# mrShark_13.net
KiCad netlist of a schematic drawn in EAGLE
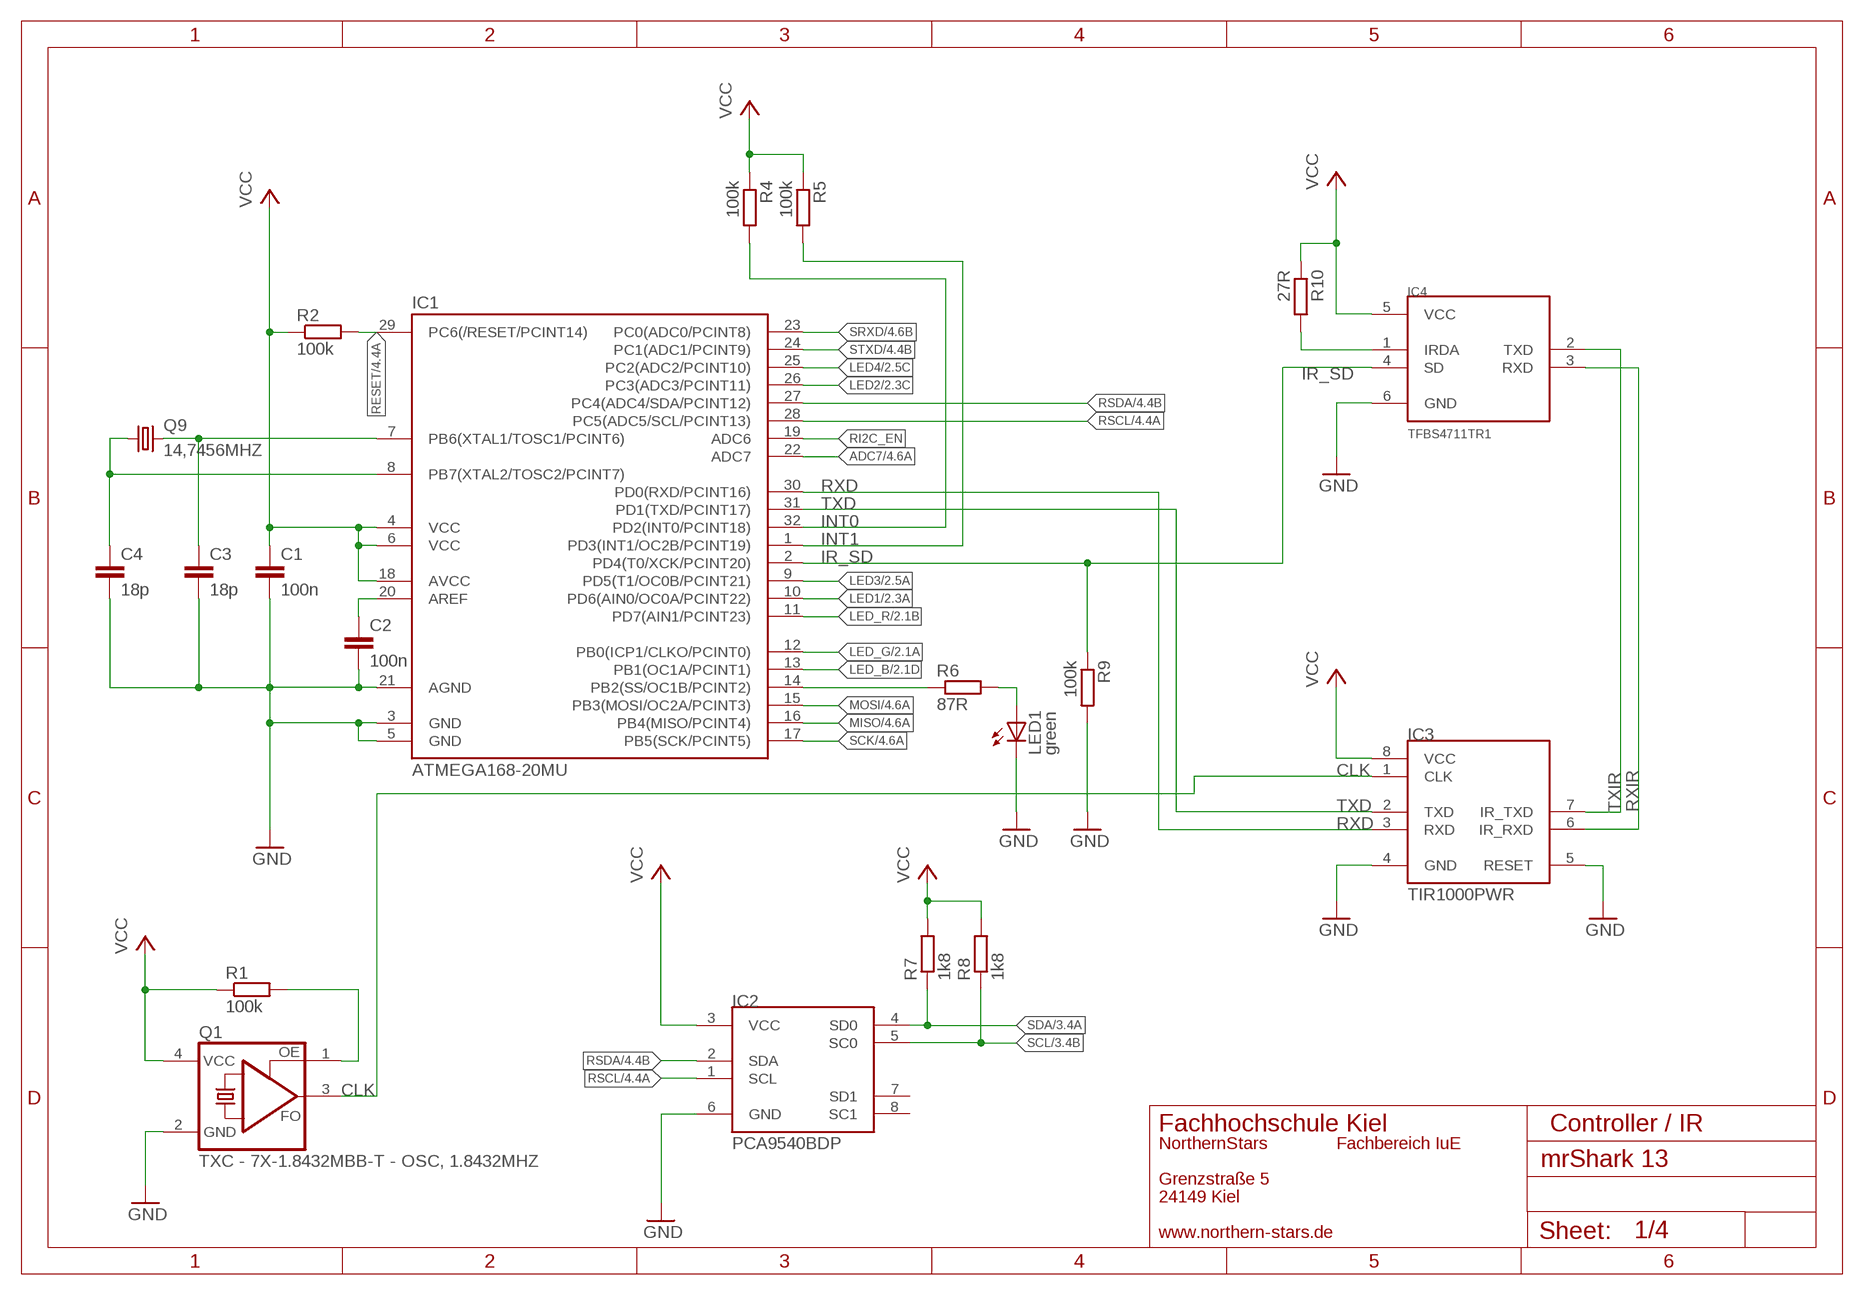
[diagram p0: schematic, sheet 1]
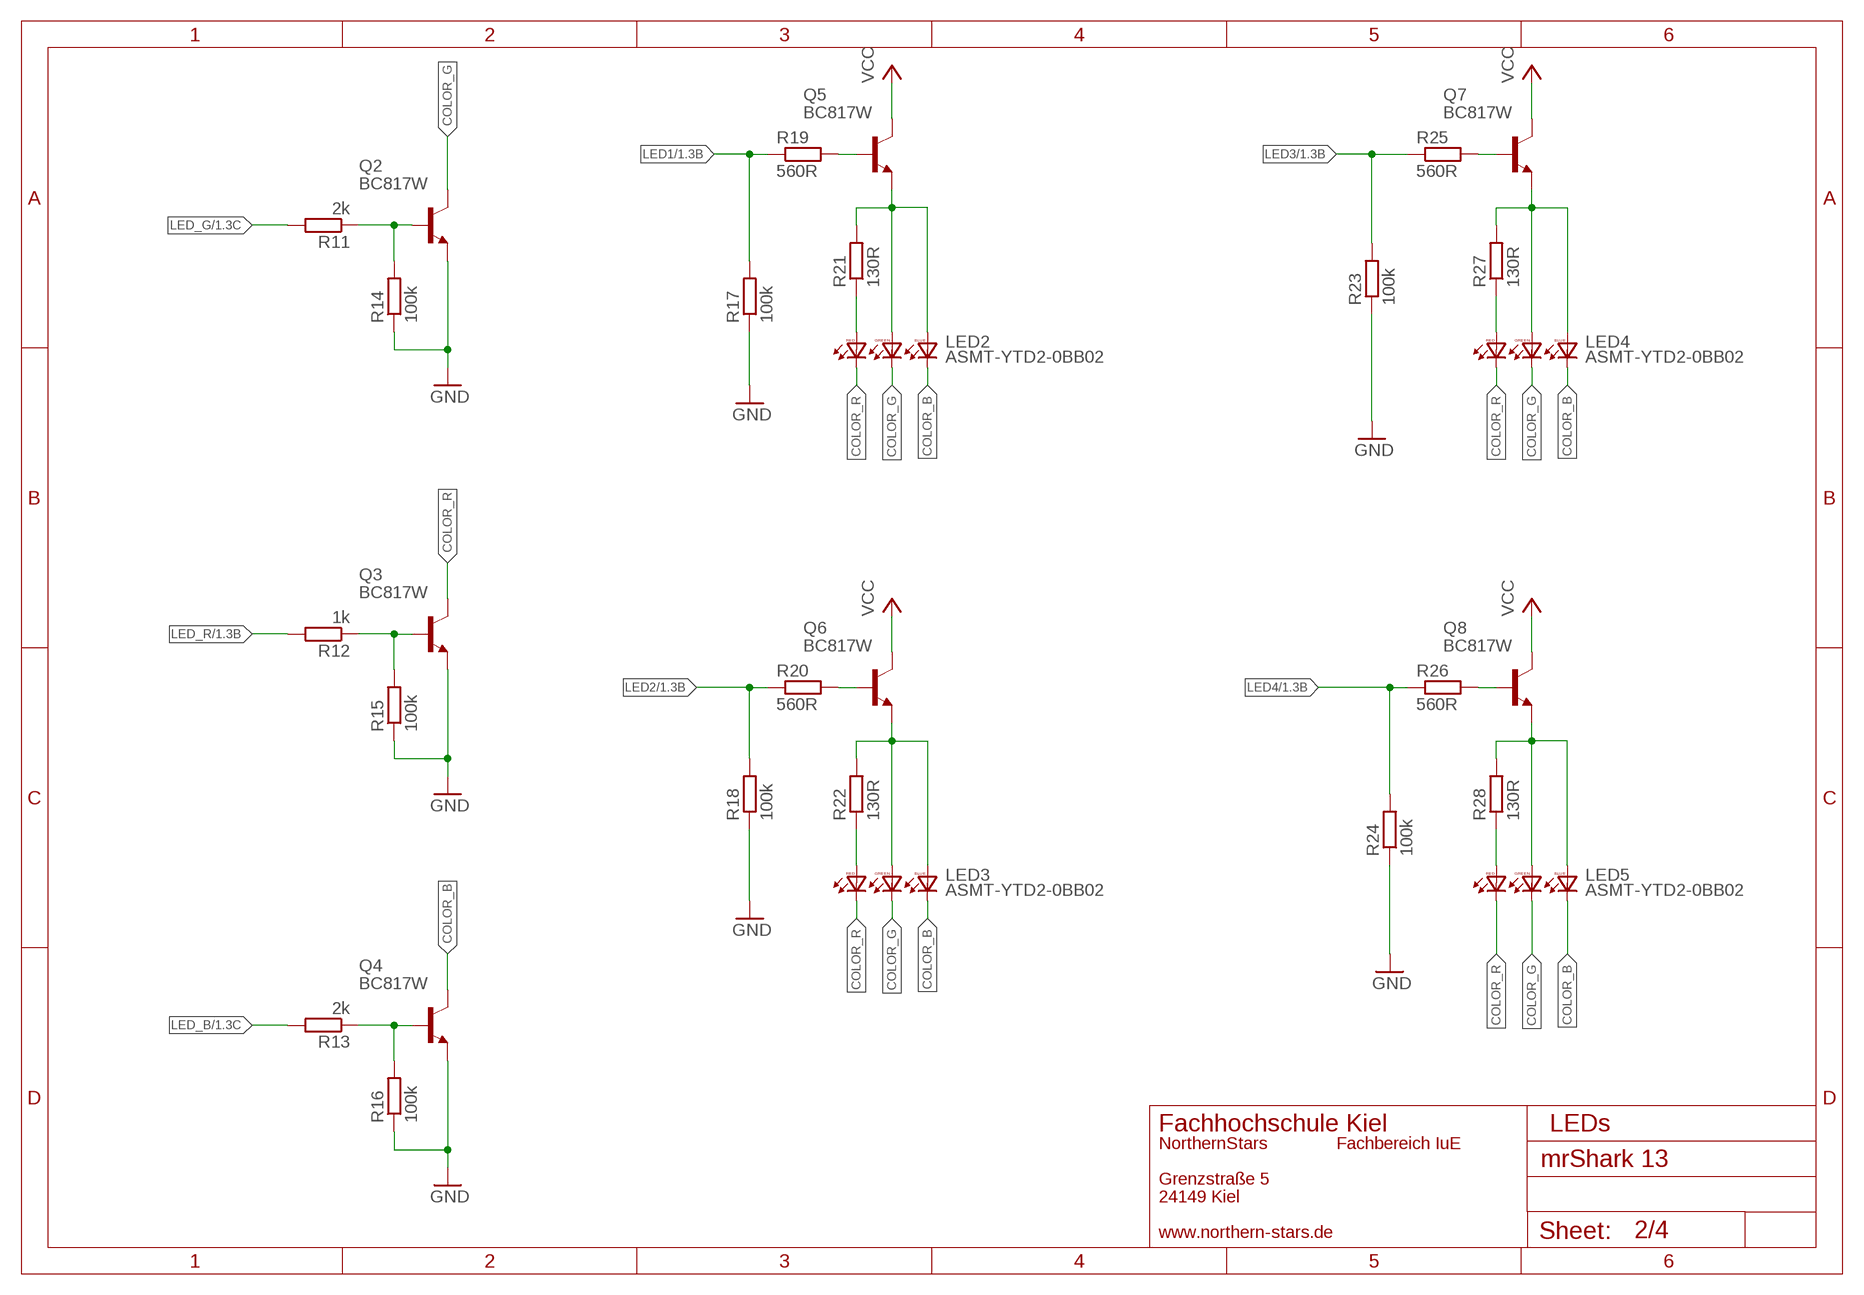
[diagram p1: schematic, sheet 2]
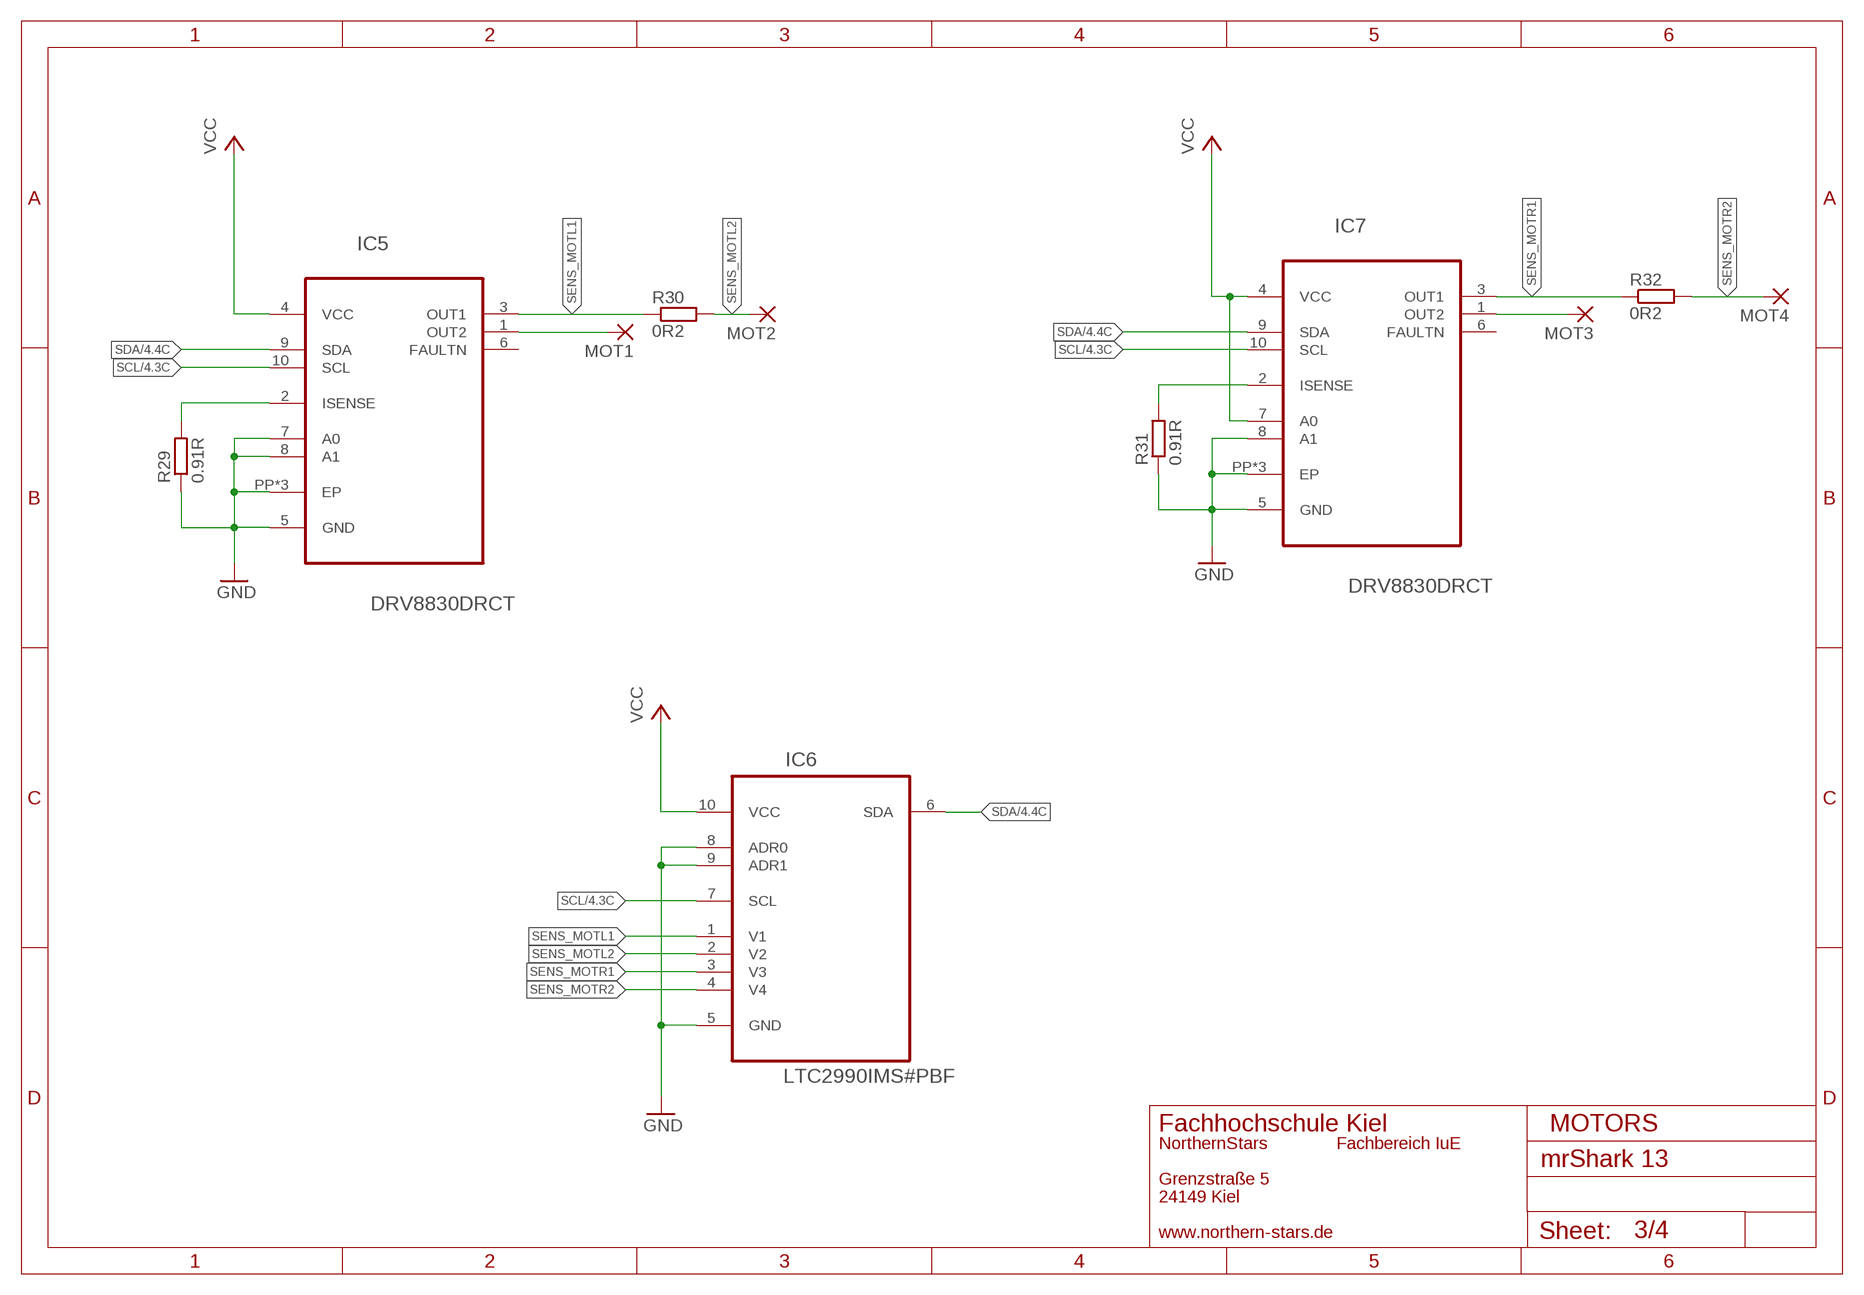
[diagram p2: schematic, sheet 3]
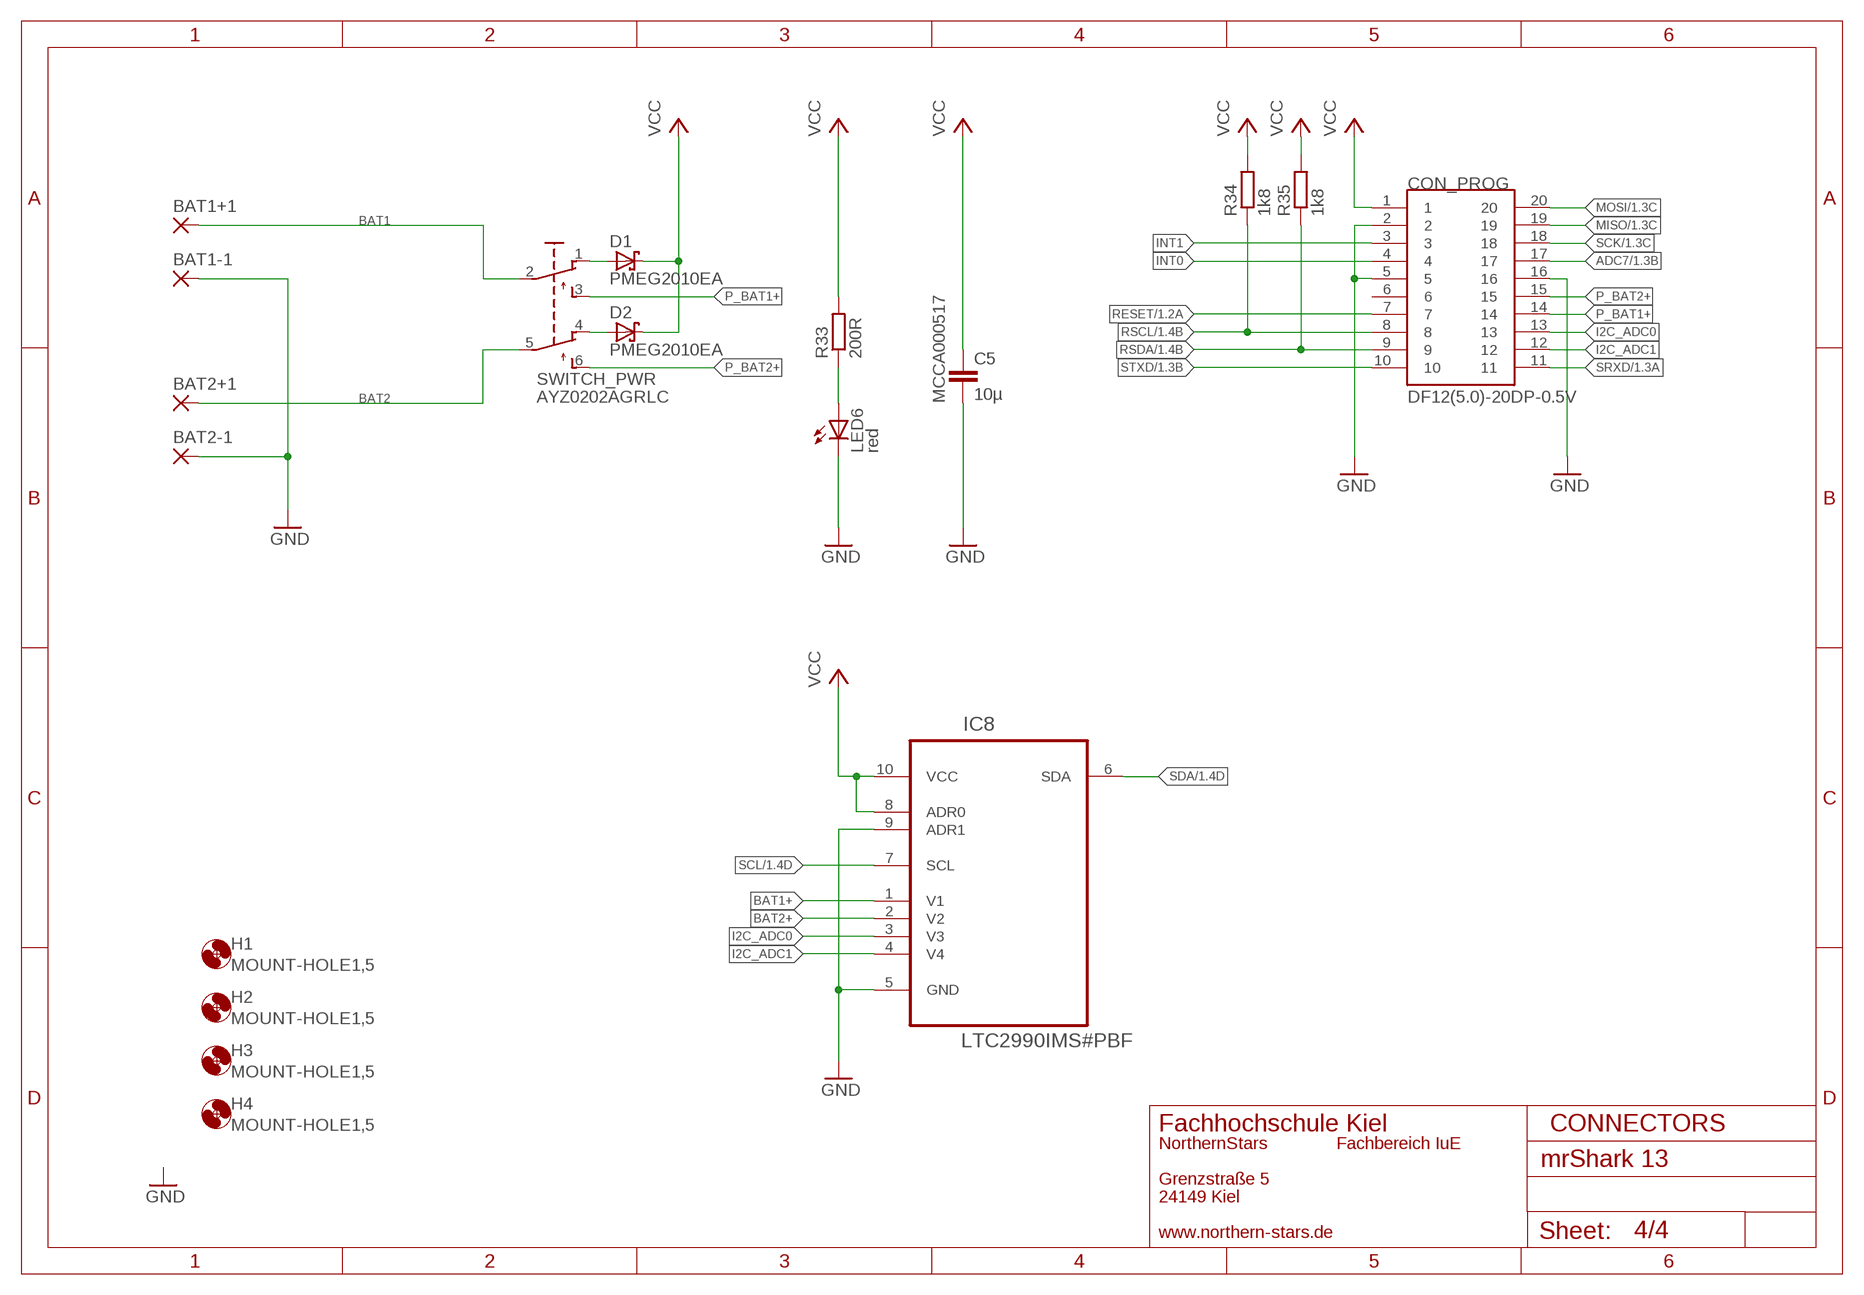
[diagram p3: schematic, sheet 4]

(export (version "E")
  (design (tool "Eeschema 10.0.6"))
  (components
    (comp (ref "C1")
      (value "100n")
      (footprint "eagle-import:C0201")
      (libsource (lib "eagle-import") (part "C-EUC0201"))
    )
    (comp (ref "C2")
      (value "100n")
      (footprint "eagle-import:C0201")
      (libsource (lib "eagle-import") (part "C-EUC0201"))
    )
    (comp (ref "C3")
      (value "18p")
      (footprint "eagle-import:C0201")
      (libsource (lib "eagle-import") (part "C-EUC0201"))
    )
    (comp (ref "C4")
      (value "18p")
      (footprint "eagle-import:C0201")
      (libsource (lib "eagle-import") (part "C-EUC0201"))
    )
    (comp (ref "IC1")
      (value "ATMEGA168-20MU")
      (footprint "eagle-import:MLF32")
      (libsource (lib "eagle-import") (part "ATMEGA48/88/168-MU"))
    )
    (comp (ref "IC2")
      (value "PCA9540BDP")
      (footprint "eagle-import:TSSOP8")
      (libsource (lib "eagle-import") (part "PCA9540TSSOP8"))
    )
    (comp (ref "IC3")
      (value "TIR1000PWR")
      (footprint "eagle-import:PW_R-PDSO-G08")
      (libsource (lib "eagle-import") (part "TIR1000PWR"))
    )
    (comp (ref "IC4")
      (value "TFBS4711TR1")
      (footprint "eagle-import:TFBS4711")
      (libsource (lib "eagle-import") (part "TFBS4711TR1"))
    )
    (comp (ref "LED1")
      (value "green")
      (footprint "eagle-import:CHIPLED_0603")
      (libsource (lib "eagle-import") (part "LEDCHIPLED_0603"))
    )
    (comp (ref "Q1")
      (value "TXC - 7X-1.8432MBB-T - OSC, 1.8432MHZ")
      (footprint "eagle-import:3.2X2.5")
      (libsource (lib "eagle-import") (part "7X-SERIES"))
    )
    (comp (ref "Q9")
      (value "14,7456MHZ")
      (footprint "eagle-import:TXC_7B_SERIES")
      (libsource (lib "eagle-import") (part "TXC-7B-SERIESSMD"))
    )
    (comp (ref "R1")
      (value "100k")
      (footprint "eagle-import:R0201")
      (libsource (lib "eagle-import") (part "R-EU_R0201"))
    )
    (comp (ref "R2")
      (value "100k")
      (footprint "eagle-import:R0201")
      (libsource (lib "eagle-import") (part "R-EU_R0201"))
    )
    (comp (ref "R4")
      (value "100k")
      (footprint "eagle-import:R0201")
      (libsource (lib "eagle-import") (part "R-EU_R0201"))
    )
    (comp (ref "R5")
      (value "100k")
      (footprint "eagle-import:R0201")
      (libsource (lib "eagle-import") (part "R-EU_R0201"))
    )
    (comp (ref "R6")
      (value "87R")
      (footprint "eagle-import:R0201")
      (libsource (lib "eagle-import") (part "R-EU_R0201"))
    )
    (comp (ref "R7")
      (value "1k8")
      (footprint "eagle-import:R0201")
      (libsource (lib "eagle-import") (part "R-EU_R0201"))
    )
    (comp (ref "R8")
      (value "1k8")
      (footprint "eagle-import:R0201")
      (libsource (lib "eagle-import") (part "R-EU_R0201"))
    )
    (comp (ref "R9")
      (value "100k")
      (footprint "eagle-import:R0201")
      (libsource (lib "eagle-import") (part "R-EU_R0201"))
    )
    (comp (ref "R10")
      (value "27R")
      (footprint "eagle-import:R0201")
      (libsource (lib "eagle-import") (part "R-EU_R0201"))
    )
    (comp (ref "IC5")
      (value "DRV8830DRCT")
      (footprint "eagle-import:S-PDSO-N10")
      (libsource (lib "eagle-import") (part "DRV8830DGQRWSON"))
    )
    (comp (ref "IC6")
      (value "LTC2990IMS#PBF")
      (footprint "eagle-import:SOP50P490X110-10N")
      (libsource (lib "eagle-import") (part "LTC2990IMSPBF"))
    )
    (comp (ref "IC7")
      (value "DRV8830DRCT")
      (footprint "eagle-import:S-PDSO-N10")
      (libsource (lib "eagle-import") (part "DRV8830DGQRWSON"))
    )
    (comp (ref "MOT1")
      (value "1,6/0,9")
      (footprint "eagle-import:1,6_0,9")
      (libsource (lib "eagle-import") (part "1,6/0,9"))
    )
    (comp (ref "MOT2")
      (value "1,6/0,9")
      (footprint "eagle-import:1,6_0,9")
      (libsource (lib "eagle-import") (part "1,6/0,9"))
    )
    (comp (ref "MOT3")
      (value "1,6/0,9")
      (footprint "eagle-import:1,6_0,9")
      (libsource (lib "eagle-import") (part "1,6/0,9"))
    )
    (comp (ref "MOT4")
      (value "1,6/0,9")
      (footprint "eagle-import:1,6_0,9")
      (libsource (lib "eagle-import") (part "1,6/0,9"))
    )
    (comp (ref "R29")
      (value "0.91R")
      (footprint "eagle-import:R0603")
      (libsource (lib "eagle-import") (part "R-EU_R0603"))
    )
    (comp (ref "R30")
      (value "0R2")
      (footprint "eagle-import:R0603")
      (libsource (lib "eagle-import") (part "R-EU_R0603"))
    )
    (comp (ref "R31")
      (value "0.91R")
      (footprint "eagle-import:R0603")
      (libsource (lib "eagle-import") (part "R-EU_R0603"))
    )
    (comp (ref "R32")
      (value "0R2")
      (footprint "eagle-import:R0603")
      (libsource (lib "eagle-import") (part "R-EU_R0603"))
    )
    (comp (ref "BAT1+1")
      (value "1,6/0,9")
      (footprint "eagle-import:1,6_0,9")
      (libsource (lib "eagle-import") (part "1,6/0,9"))
    )
    (comp (ref "BAT1-1")
      (value "1,6/0,9")
      (footprint "eagle-import:1,6_0,9")
      (libsource (lib "eagle-import") (part "1,6/0,9"))
    )
    (comp (ref "BAT2+1")
      (value "1,6/0,9")
      (footprint "eagle-import:1,6_0,9")
      (libsource (lib "eagle-import") (part "1,6/0,9"))
    )
    (comp (ref "BAT2-1")
      (value "1,6/0,9")
      (footprint "eagle-import:1,6_0,9")
      (libsource (lib "eagle-import") (part "1,6/0,9"))
    )
    (comp (ref "C5")
      (value "10µ")
      (footprint "eagle-import:C0603K")
      (libsource (lib "eagle-import") (part "C-EUC0603K"))
    )
    (comp (ref "CON_PROG")
      (value "DF12(5.0)-20DP-0.5V")
      (footprint "eagle-import:DF12-20DP")
      (libsource (lib "eagle-import") (part "DF12-20DP"))
    )
    (comp (ref "D1")
      (value "PMEG2010EA")
      (footprint "eagle-import:SOD323-R")
      (libsource (lib "eagle-import") (part "PMEG2010EAR"))
    )
    (comp (ref "D2")
      (value "PMEG2010EA")
      (footprint "eagle-import:SOD323-R")
      (libsource (lib "eagle-import") (part "PMEG2010EAR"))
    )
    (comp (ref "H1")
      (value "MOUNT-HOLE1,5")
      (footprint "eagle-import:1,5")
      (libsource (lib "eagle-import") (part "MOUNT-HOLE1,5"))
    )
    (comp (ref "H2")
      (value "MOUNT-HOLE1,5")
      (footprint "eagle-import:1,5")
      (libsource (lib "eagle-import") (part "MOUNT-HOLE1,5"))
    )
    (comp (ref "H3")
      (value "MOUNT-HOLE1,5")
      (footprint "eagle-import:1,5")
      (libsource (lib "eagle-import") (part "MOUNT-HOLE1,5"))
    )
    (comp (ref "H4")
      (value "MOUNT-HOLE1,5")
      (footprint "eagle-import:1,5")
      (libsource (lib "eagle-import") (part "MOUNT-HOLE1,5"))
    )
    (comp (ref "IC8")
      (value "LTC2990IMS#PBF")
      (footprint "eagle-import:SOP50P490X110-10N")
      (libsource (lib "eagle-import") (part "LTC2990IMSPBF"))
    )
    (comp (ref "LED6")
      (value "red")
      (footprint "eagle-import:CHIPLED_0603")
      (libsource (lib "eagle-import") (part "LEDCHIPLED_0603"))
    )
    (comp (ref "R33")
      (value "200R")
      (footprint "eagle-import:R0201")
      (libsource (lib "eagle-import") (part "R-EU_R0201"))
    )
    (comp (ref "R34")
      (value "1k8")
      (footprint "eagle-import:R0201")
      (libsource (lib "eagle-import") (part "R-EU_R0201"))
    )
    (comp (ref "R35")
      (value "1k8")
      (footprint "eagle-import:R0201")
      (libsource (lib "eagle-import") (part "R-EU_R0201"))
    )
    (comp (ref "SWITCH_PWR")
      (value "AYZ0202AGRLC")
      (footprint "eagle-import:AYZ0202AGLRC")
      (libsource (lib "eagle-import") (part "AYZ0202AGRLC"))
    )
    (comp (ref "LED2")
      (value "ASMT-YTD2-0BB02")
      (footprint "eagle-import:PLCC6K")
      (libsource (lib "eagle-import") (part "PLCC6K"))
    )
    (comp (ref "LED3")
      (value "ASMT-YTD2-0BB02")
      (footprint "eagle-import:PLCC6K")
      (libsource (lib "eagle-import") (part "PLCC6K"))
    )
    (comp (ref "LED4")
      (value "ASMT-YTD2-0BB02")
      (footprint "eagle-import:PLCC6K")
      (libsource (lib "eagle-import") (part "PLCC6K"))
    )
    (comp (ref "LED5")
      (value "ASMT-YTD2-0BB02")
      (footprint "eagle-import:PLCC6K")
      (libsource (lib "eagle-import") (part "PLCC6K"))
    )
    (comp (ref "Q2")
      (value "BC817W")
      (footprint "eagle-import:SOT323-BEC")
      (libsource (lib "eagle-import") (part "BC817W"))
    )
    (comp (ref "Q3")
      (value "BC817W")
      (footprint "eagle-import:SOT323-BEC")
      (libsource (lib "eagle-import") (part "BC817W"))
    )
    (comp (ref "Q4")
      (value "BC817W")
      (footprint "eagle-import:SOT323-BEC")
      (libsource (lib "eagle-import") (part "BC817W"))
    )
    (comp (ref "Q5")
      (value "BC817W")
      (footprint "eagle-import:SOT323-BEC")
      (libsource (lib "eagle-import") (part "BC817W"))
    )
    (comp (ref "Q6")
      (value "BC817W")
      (footprint "eagle-import:SOT323-BEC")
      (libsource (lib "eagle-import") (part "BC817W"))
    )
    (comp (ref "Q7")
      (value "BC817W")
      (footprint "eagle-import:SOT323-BEC")
      (libsource (lib "eagle-import") (part "BC817W"))
    )
    (comp (ref "Q8")
      (value "BC817W")
      (footprint "eagle-import:SOT323-BEC")
      (libsource (lib "eagle-import") (part "BC817W"))
    )
    (comp (ref "R11")
      (value "2k")
      (footprint "eagle-import:R0201")
      (libsource (lib "eagle-import") (part "R-EU_R0201"))
    )
    (comp (ref "R12")
      (value "1k")
      (footprint "eagle-import:R0201")
      (libsource (lib "eagle-import") (part "R-EU_R0201"))
    )
    (comp (ref "R13")
      (value "2k")
      (footprint "eagle-import:R0201")
      (libsource (lib "eagle-import") (part "R-EU_R0201"))
    )
    (comp (ref "R14")
      (value "100k")
      (footprint "eagle-import:R0201")
      (libsource (lib "eagle-import") (part "R-EU_R0201"))
    )
    (comp (ref "R15")
      (value "100k")
      (footprint "eagle-import:R0201")
      (libsource (lib "eagle-import") (part "R-EU_R0201"))
    )
    (comp (ref "R16")
      (value "100k")
      (footprint "eagle-import:R0201")
      (libsource (lib "eagle-import") (part "R-EU_R0201"))
    )
    (comp (ref "R17")
      (value "100k")
      (footprint "eagle-import:R0201")
      (libsource (lib "eagle-import") (part "R-EU_R0201"))
    )
    (comp (ref "R18")
      (value "100k")
      (footprint "eagle-import:R0201")
      (libsource (lib "eagle-import") (part "R-EU_R0201"))
    )
    (comp (ref "R19")
      (value "560R")
      (footprint "eagle-import:R0201")
      (libsource (lib "eagle-import") (part "R-EU_R0201"))
    )
    (comp (ref "R20")
      (value "560R")
      (footprint "eagle-import:R0201")
      (libsource (lib "eagle-import") (part "R-EU_R0201"))
    )
    (comp (ref "R21")
      (value "130R")
      (footprint "eagle-import:R0201")
      (libsource (lib "eagle-import") (part "R-EU_R0201"))
    )
    (comp (ref "R22")
      (value "130R")
      (footprint "eagle-import:R0201")
      (libsource (lib "eagle-import") (part "R-EU_R0201"))
    )
    (comp (ref "R23")
      (value "100k")
      (footprint "eagle-import:R0201")
      (libsource (lib "eagle-import") (part "R-EU_R0201"))
    )
    (comp (ref "R24")
      (value "100k")
      (footprint "eagle-import:R0201")
      (libsource (lib "eagle-import") (part "R-EU_R0201"))
    )
    (comp (ref "R25")
      (value "560R")
      (footprint "eagle-import:R0201")
      (libsource (lib "eagle-import") (part "R-EU_R0201"))
    )
    (comp (ref "R26")
      (value "560R")
      (footprint "eagle-import:R0201")
      (libsource (lib "eagle-import") (part "R-EU_R0201"))
    )
    (comp (ref "R27")
      (value "130R")
      (footprint "eagle-import:R0201")
      (libsource (lib "eagle-import") (part "R-EU_R0201"))
    )
    (comp (ref "R28")
      (value "130R")
      (footprint "eagle-import:R0201")
      (libsource (lib "eagle-import") (part "R-EU_R0201"))
    )
  )
  (nets
    (net (code "1") (name "ADC7") (class "Default")
      (node (ref "CON_PROG") (pin "17") (pinfunction "17_17") (pintype "bidirectional"))
      (node (ref "IC1") (pin "22") (pinfunction "ADC7_22") (pintype "passive"))
    )
    (net (code "2") (name "BAT1") (class "Default")
      (node (ref "BAT1+1") (pin "1") (pinfunction "P_1") (pintype "passive"))
      (node (ref "SWITCH_PWR") (pin "2") (pinfunction "P_2") (pintype "passive"))
    )
    (net (code "3") (name "BAT1+") (class "Default")
      (node (ref "D1") (pin "A") (pinfunction "A_A") (pintype "passive"))
      (node (ref "IC8") (pin "1") (pinfunction "V1_1") (pintype "input"))
      (node (ref "SWITCH_PWR") (pin "1") (pinfunction "O_1") (pintype "passive"))
    )
    (net (code "4") (name "BAT2") (class "Default")
      (node (ref "BAT2+1") (pin "1") (pinfunction "P_1") (pintype "passive"))
      (node (ref "SWITCH_PWR") (pin "5") (pinfunction "P1_5") (pintype "passive"))
    )
    (net (code "5") (name "BAT2+") (class "Default")
      (node (ref "D2") (pin "A") (pinfunction "A_A") (pintype "passive"))
      (node (ref "IC8") (pin "2") (pinfunction "V2_2") (pintype "input"))
      (node (ref "SWITCH_PWR") (pin "4") (pinfunction "O1_4") (pintype "passive"))
    )
    (net (code "6") (name "CLK") (class "Default")
      (node (ref "IC3") (pin "1") (pinfunction "CLK_1") (pintype "bidirectional"))
      (node (ref "Q1") (pin "3") (pinfunction "FO_3") (pintype "output"))
    )
    (net (code "7") (name "COLOR_B") (class "Default")
      (node (ref "LED2") (pin "1") (pinfunction "BC_1") (pintype "passive"))
      (node (ref "LED3") (pin "1") (pinfunction "BC_1") (pintype "passive"))
      (node (ref "LED4") (pin "1") (pinfunction "BC_1") (pintype "passive"))
      (node (ref "LED5") (pin "1") (pinfunction "BC_1") (pintype "passive"))
      (node (ref "Q4") (pin "C") (pinfunction "C_C") (pintype "passive"))
    )
    (net (code "8") (name "COLOR_G") (class "Default")
      (node (ref "LED2") (pin "2") (pinfunction "GC_2") (pintype "passive"))
      (node (ref "LED3") (pin "2") (pinfunction "GC_2") (pintype "passive"))
      (node (ref "LED4") (pin "2") (pinfunction "GC_2") (pintype "passive"))
      (node (ref "LED5") (pin "2") (pinfunction "GC_2") (pintype "passive"))
      (node (ref "Q2") (pin "C") (pinfunction "C_C") (pintype "passive"))
    )
    (net (code "9") (name "COLOR_R") (class "Default")
      (node (ref "LED2") (pin "3") (pinfunction "RC_3") (pintype "passive"))
      (node (ref "LED3") (pin "3") (pinfunction "RC_3") (pintype "passive"))
      (node (ref "LED4") (pin "3") (pinfunction "RC_3") (pintype "passive"))
      (node (ref "LED5") (pin "3") (pinfunction "RC_3") (pintype "passive"))
      (node (ref "Q3") (pin "C") (pinfunction "C_C") (pintype "passive"))
    )
    (net (code "10") (name "GND") (class "Default")
      (node (ref "BAT1-1") (pin "1") (pinfunction "P_1") (pintype "passive"))
      (node (ref "BAT2-1") (pin "1") (pinfunction "P_1") (pintype "passive"))
      (node (ref "C1") (pin "2") (pinfunction "2_2") (pintype "passive"))
      (node (ref "C2") (pin "2") (pinfunction "2_2") (pintype "passive"))
      (node (ref "C3") (pin "2") (pinfunction "2_2") (pintype "passive"))
      (node (ref "C4") (pin "2") (pinfunction "2_2") (pintype "passive"))
      (node (ref "C5") (pin "2") (pinfunction "2_2") (pintype "passive"))
      (node (ref "CON_PROG") (pin "16") (pinfunction "16_16") (pintype "bidirectional"))
      (node (ref "CON_PROG") (pin "2") (pinfunction "2_2") (pintype "bidirectional"))
      (node (ref "CON_PROG") (pin "5") (pinfunction "5_5") (pintype "bidirectional"))
      (node (ref "IC1") (pin "21") (pinfunction "AGND_21") (pintype "power_in"))
      (node (ref "IC1") (pin "3") (pinfunction "GND_3") (pintype "power_in"))
      (node (ref "IC1") (pin "5") (pinfunction "GND_5") (pintype "power_in"))
      (node (ref "IC2") (pin "6") (pinfunction "GND_6") (pintype "bidirectional"))
      (node (ref "IC3") (pin "4") (pinfunction "GND_4") (pintype "bidirectional"))
      (node (ref "IC3") (pin "5") (pinfunction "RESET_5") (pintype "bidirectional"))
      (node (ref "IC4") (pin "6") (pinfunction "GND_6") (pintype "bidirectional"))
      (node (ref "IC5") (pin "5") (pinfunction "GND_5") (pintype "passive"))
      (node (ref "IC5") (pin "7") (pinfunction "A0_7") (pintype "input"))
      (node (ref "IC5") (pin "8") (pinfunction "A1_8") (pintype "input"))
      (node (ref "IC5") (pin "PP") (pinfunction "EP_PP") (pintype "passive"))
      (node (ref "IC5") (pin "PP@1") (pinfunction "EP_PP@1") (pintype "passive"))
      (node (ref "IC5") (pin "PP@2") (pinfunction "EP_PP@2") (pintype "passive"))
      (node (ref "IC6") (pin "5") (pinfunction "GND_5") (pintype "passive"))
      (node (ref "IC6") (pin "8") (pinfunction "ADR0_8") (pintype "input"))
      (node (ref "IC6") (pin "9") (pinfunction "ADR1_9") (pintype "input"))
      (node (ref "IC7") (pin "5") (pinfunction "GND_5") (pintype "passive"))
      (node (ref "IC7") (pin "8") (pinfunction "A1_8") (pintype "input"))
      (node (ref "IC7") (pin "PP") (pinfunction "EP_PP") (pintype "passive"))
      (node (ref "IC7") (pin "PP@1") (pinfunction "EP_PP@1") (pintype "passive"))
      (node (ref "IC7") (pin "PP@2") (pinfunction "EP_PP@2") (pintype "passive"))
      (node (ref "IC8") (pin "5") (pinfunction "GND_5") (pintype "passive"))
      (node (ref "IC8") (pin "9") (pinfunction "ADR1_9") (pintype "input"))
      (node (ref "LED1") (pin "C") (pinfunction "C_C") (pintype "passive"))
      (node (ref "LED6") (pin "C") (pinfunction "C_C") (pintype "passive"))
      (node (ref "Q1") (pin "2") (pinfunction "GND_2") (pintype "power_in"))
      (node (ref "Q2") (pin "E") (pinfunction "E_E") (pintype "passive"))
      (node (ref "Q3") (pin "E") (pinfunction "E_E") (pintype "passive"))
      (node (ref "Q4") (pin "E") (pinfunction "E_E") (pintype "passive"))
      (node (ref "R14") (pin "1") (pinfunction "1_1") (pintype "passive"))
      (node (ref "R15") (pin "1") (pinfunction "1_1") (pintype "passive"))
      (node (ref "R16") (pin "1") (pinfunction "1_1") (pintype "passive"))
      (node (ref "R17") (pin "1") (pinfunction "1_1") (pintype "passive"))
      (node (ref "R18") (pin "1") (pinfunction "1_1") (pintype "passive"))
      (node (ref "R23") (pin "1") (pinfunction "1_1") (pintype "passive"))
      (node (ref "R24") (pin "1") (pinfunction "1_1") (pintype "passive"))
      (node (ref "R29") (pin "1") (pinfunction "1_1") (pintype "passive"))
      (node (ref "R31") (pin "1") (pinfunction "1_1") (pintype "passive"))
      (node (ref "R9") (pin "2") (pinfunction "2_2") (pintype "passive"))
    )
    (net (code "11") (name "I2C_ADC0") (class "Default")
      (node (ref "CON_PROG") (pin "13") (pinfunction "13_13") (pintype "bidirectional"))
      (node (ref "IC8") (pin "3") (pinfunction "V3_3") (pintype "input"))
    )
    (net (code "12") (name "I2C_ADC1") (class "Default")
      (node (ref "CON_PROG") (pin "12") (pinfunction "12_12") (pintype "bidirectional"))
      (node (ref "IC8") (pin "4") (pinfunction "V4_4") (pintype "input"))
    )
    (net (code "13") (name "INT0") (class "Default")
      (node (ref "CON_PROG") (pin "4") (pinfunction "4_4") (pintype "bidirectional"))
      (node (ref "IC1") (pin "32") (pinfunction "PD2(INT0/PCINT18)_32") (pintype "bidirectional"))
      (node (ref "R4") (pin "2") (pinfunction "2_2") (pintype "passive"))
    )
    (net (code "14") (name "INT1") (class "Default")
      (node (ref "CON_PROG") (pin "3") (pinfunction "3_3") (pintype "bidirectional"))
      (node (ref "IC1") (pin "1") (pinfunction "PD3(INT1/OC2B/PCINT19)_1") (pintype "bidirectional"))
      (node (ref "R5") (pin "2") (pinfunction "2_2") (pintype "passive"))
    )
    (net (code "15") (name "IR_SD") (class "Default")
      (node (ref "IC1") (pin "2") (pinfunction "PD4(T0/XCK/PCINT20)_2") (pintype "bidirectional"))
      (node (ref "IC4") (pin "4") (pinfunction "SD_4") (pintype "bidirectional"))
      (node (ref "R9") (pin "1") (pinfunction "1_1") (pintype "passive"))
    )
    (net (code "16") (name "LED1") (class "Default")
      (node (ref "IC1") (pin "10") (pinfunction "PD6(AIN0/OC0A/PCINT22)_10") (pintype "bidirectional"))
      (node (ref "R17") (pin "2") (pinfunction "2_2") (pintype "passive"))
      (node (ref "R19") (pin "1") (pinfunction "1_1") (pintype "passive"))
    )
    (net (code "17") (name "LED2") (class "Default")
      (node (ref "IC1") (pin "26") (pinfunction "PC3(ADC3/PCINT11)_26") (pintype "bidirectional"))
      (node (ref "R18") (pin "2") (pinfunction "2_2") (pintype "passive"))
      (node (ref "R20") (pin "1") (pinfunction "1_1") (pintype "passive"))
    )
    (net (code "18") (name "LED3") (class "Default")
      (node (ref "IC1") (pin "9") (pinfunction "PD5(T1/OC0B/PCINT21)_9") (pintype "bidirectional"))
      (node (ref "R23") (pin "2") (pinfunction "2_2") (pintype "passive"))
      (node (ref "R25") (pin "1") (pinfunction "1_1") (pintype "passive"))
    )
    (net (code "19") (name "LED4") (class "Default")
      (node (ref "IC1") (pin "25") (pinfunction "PC2(ADC2/PCINT10)_25") (pintype "bidirectional"))
      (node (ref "R24") (pin "2") (pinfunction "2_2") (pintype "passive"))
      (node (ref "R26") (pin "1") (pinfunction "1_1") (pintype "passive"))
    )
    (net (code "20") (name "LED_B") (class "Default")
      (node (ref "IC1") (pin "13") (pinfunction "PB1(OC1A/PCINT1)_13") (pintype "bidirectional"))
      (node (ref "R13") (pin "2") (pinfunction "2_2") (pintype "passive"))
    )
    (net (code "21") (name "LED_G") (class "Default")
      (node (ref "IC1") (pin "12") (pinfunction "PB0(ICP1/CLKO/PCINT0)_12") (pintype "bidirectional"))
      (node (ref "R11") (pin "2") (pinfunction "2_2") (pintype "passive"))
    )
    (net (code "22") (name "LED_R") (class "Default")
      (node (ref "IC1") (pin "11") (pinfunction "PD7(AIN1/PCINT23)_11") (pintype "bidirectional"))
      (node (ref "R12") (pin "2") (pinfunction "2_2") (pintype "passive"))
    )
    (net (code "23") (name "MISO") (class "Default")
      (node (ref "CON_PROG") (pin "19") (pinfunction "19_19") (pintype "bidirectional"))
      (node (ref "IC1") (pin "16") (pinfunction "PB4(MISO/PCINT4)_16") (pintype "bidirectional"))
    )
    (net (code "24") (name "MOSI") (class "Default")
      (node (ref "CON_PROG") (pin "20") (pinfunction "20_20") (pintype "bidirectional"))
      (node (ref "IC1") (pin "15") (pinfunction "PB3(MOSI/OC2A/PCINT3)_15") (pintype "bidirectional"))
    )
    (net (code "25") (name "Net-(IC1-AREF)") (class "Default")
      (node (ref "C2") (pin "1") (pinfunction "1_1") (pintype "passive"))
      (node (ref "IC1") (pin "20") (pinfunction "AREF_20") (pintype "passive"))
    )
    (net (code "26") (name "Net-(IC1-PB2(SS{slash}OC1B{slash}PCINT2))") (class "Default")
      (node (ref "IC1") (pin "14") (pinfunction "PB2(SS/OC1B/PCINT2)_14") (pintype "bidirectional"))
      (node (ref "R6") (pin "1") (pinfunction "1_1") (pintype "passive"))
    )
    (net (code "27") (name "Net-(IC1-PB6(XTAL1{slash}TOSC1{slash}PCINT6))") (class "Default")
      (node (ref "C3") (pin "1") (pinfunction "1_1") (pintype "passive"))
      (node (ref "IC1") (pin "7") (pinfunction "PB6(XTAL1/TOSC1/PCINT6)_7") (pintype "bidirectional"))
      (node (ref "Q9") (pin "3") (pinfunction "2_3") (pintype "passive"))
    )
    (net (code "28") (name "Net-(IC1-PB7(XTAL2{slash}TOSC2{slash}PCINT7))") (class "Default")
      (node (ref "C4") (pin "1") (pinfunction "1_1") (pintype "passive"))
      (node (ref "IC1") (pin "8") (pinfunction "PB7(XTAL2/TOSC2/PCINT7)_8") (pintype "bidirectional"))
      (node (ref "Q9") (pin "1") (pinfunction "1_1") (pintype "passive"))
    )
    (net (code "29") (name "Net-(IC4-IRDA)") (class "Default")
      (node (ref "IC4") (pin "1") (pinfunction "IRDA_1") (pintype "bidirectional"))
      (node (ref "R10") (pin "2") (pinfunction "2_2") (pintype "passive"))
    )
    (net (code "30") (name "Net-(IC5-ISENSE)") (class "Default")
      (node (ref "IC5") (pin "2") (pinfunction "ISENSE_2") (pintype "input"))
      (node (ref "R29") (pin "2") (pinfunction "2_2") (pintype "passive"))
    )
    (net (code "31") (name "Net-(IC5-OUT2)") (class "Default")
      (node (ref "IC5") (pin "1") (pinfunction "OUT2_1") (pintype "output"))
      (node (ref "MOT1") (pin "1") (pinfunction "P_1") (pintype "passive"))
    )
    (net (code "32") (name "Net-(IC7-ISENSE)") (class "Default")
      (node (ref "IC7") (pin "2") (pinfunction "ISENSE_2") (pintype "input"))
      (node (ref "R31") (pin "2") (pinfunction "2_2") (pintype "passive"))
    )
    (net (code "33") (name "Net-(IC7-OUT2)") (class "Default")
      (node (ref "IC7") (pin "1") (pinfunction "OUT2_1") (pintype "output"))
      (node (ref "MOT3") (pin "1") (pinfunction "P_1") (pintype "passive"))
    )
    (net (code "34") (name "Net-(LED1-PadA)") (class "Default")
      (node (ref "LED1") (pin "A") (pinfunction "A_A") (pintype "passive"))
      (node (ref "R6") (pin "2") (pinfunction "2_2") (pintype "passive"))
    )
    (net (code "35") (name "Net-(LED2-BA)") (class "Default")
      (node (ref "LED2") (pin "5") (pinfunction "GA_5") (pintype "passive"))
      (node (ref "LED2") (pin "6") (pinfunction "BA_6") (pintype "passive"))
      (node (ref "Q5") (pin "E") (pinfunction "E_E") (pintype "passive"))
      (node (ref "R21") (pin "2") (pinfunction "2_2") (pintype "passive"))
    )
    (net (code "36") (name "Net-(LED2-RA)") (class "Default")
      (node (ref "LED2") (pin "4") (pinfunction "RA_4") (pintype "passive"))
      (node (ref "R21") (pin "1") (pinfunction "1_1") (pintype "passive"))
    )
    (net (code "37") (name "Net-(LED3-BA)") (class "Default")
      (node (ref "LED3") (pin "5") (pinfunction "GA_5") (pintype "passive"))
      (node (ref "LED3") (pin "6") (pinfunction "BA_6") (pintype "passive"))
      (node (ref "Q6") (pin "E") (pinfunction "E_E") (pintype "passive"))
      (node (ref "R22") (pin "2") (pinfunction "2_2") (pintype "passive"))
    )
    (net (code "38") (name "Net-(LED3-RA)") (class "Default")
      (node (ref "LED3") (pin "4") (pinfunction "RA_4") (pintype "passive"))
      (node (ref "R22") (pin "1") (pinfunction "1_1") (pintype "passive"))
    )
    (net (code "39") (name "Net-(LED4-BA)") (class "Default")
      (node (ref "LED4") (pin "5") (pinfunction "GA_5") (pintype "passive"))
      (node (ref "LED4") (pin "6") (pinfunction "BA_6") (pintype "passive"))
      (node (ref "Q7") (pin "E") (pinfunction "E_E") (pintype "passive"))
      (node (ref "R27") (pin "2") (pinfunction "2_2") (pintype "passive"))
    )
    (net (code "40") (name "Net-(LED4-RA)") (class "Default")
      (node (ref "LED4") (pin "4") (pinfunction "RA_4") (pintype "passive"))
      (node (ref "R27") (pin "1") (pinfunction "1_1") (pintype "passive"))
    )
    (net (code "41") (name "Net-(LED5-BA)") (class "Default")
      (node (ref "LED5") (pin "5") (pinfunction "GA_5") (pintype "passive"))
      (node (ref "LED5") (pin "6") (pinfunction "BA_6") (pintype "passive"))
      (node (ref "Q8") (pin "E") (pinfunction "E_E") (pintype "passive"))
      (node (ref "R28") (pin "2") (pinfunction "2_2") (pintype "passive"))
    )
    (net (code "42") (name "Net-(LED5-RA)") (class "Default")
      (node (ref "LED5") (pin "4") (pinfunction "RA_4") (pintype "passive"))
      (node (ref "R28") (pin "1") (pinfunction "1_1") (pintype "passive"))
    )
    (net (code "43") (name "Net-(LED6-PadA)") (class "Default")
      (node (ref "LED6") (pin "A") (pinfunction "A_A") (pintype "passive"))
      (node (ref "R33") (pin "1") (pinfunction "1_1") (pintype "passive"))
    )
    (net (code "44") (name "Net-(Q1-OE)") (class "Default")
      (node (ref "Q1") (pin "1") (pinfunction "OE_1") (pintype "input"))
      (node (ref "R1") (pin "2") (pinfunction "2_2") (pintype "passive"))
    )
    (net (code "45") (name "Net-(Q2-PadB)") (class "Default")
      (node (ref "Q2") (pin "B") (pinfunction "B_B") (pintype "passive"))
      (node (ref "R11") (pin "1") (pinfunction "1_1") (pintype "passive"))
      (node (ref "R14") (pin "2") (pinfunction "2_2") (pintype "passive"))
    )
    (net (code "46") (name "Net-(Q3-PadB)") (class "Default")
      (node (ref "Q3") (pin "B") (pinfunction "B_B") (pintype "passive"))
      (node (ref "R12") (pin "1") (pinfunction "1_1") (pintype "passive"))
      (node (ref "R15") (pin "2") (pinfunction "2_2") (pintype "passive"))
    )
    (net (code "47") (name "Net-(Q4-PadB)") (class "Default")
      (node (ref "Q4") (pin "B") (pinfunction "B_B") (pintype "passive"))
      (node (ref "R13") (pin "1") (pinfunction "1_1") (pintype "passive"))
      (node (ref "R16") (pin "2") (pinfunction "2_2") (pintype "passive"))
    )
    (net (code "48") (name "Net-(Q5-PadB)") (class "Default")
      (node (ref "Q5") (pin "B") (pinfunction "B_B") (pintype "passive"))
      (node (ref "R19") (pin "2") (pinfunction "2_2") (pintype "passive"))
    )
    (net (code "49") (name "Net-(Q6-PadB)") (class "Default")
      (node (ref "Q6") (pin "B") (pinfunction "B_B") (pintype "passive"))
      (node (ref "R20") (pin "2") (pinfunction "2_2") (pintype "passive"))
    )
    (net (code "50") (name "Net-(Q7-PadB)") (class "Default")
      (node (ref "Q7") (pin "B") (pinfunction "B_B") (pintype "passive"))
      (node (ref "R25") (pin "2") (pinfunction "2_2") (pintype "passive"))
    )
    (net (code "51") (name "Net-(Q8-PadB)") (class "Default")
      (node (ref "Q8") (pin "B") (pinfunction "B_B") (pintype "passive"))
      (node (ref "R26") (pin "2") (pinfunction "2_2") (pintype "passive"))
    )
    (net (code "52") (name "P_BAT1+") (class "Default")
      (node (ref "CON_PROG") (pin "14") (pinfunction "14_14") (pintype "bidirectional"))
      (node (ref "SWITCH_PWR") (pin "3") (pinfunction "S_3") (pintype "passive"))
    )
    (net (code "53") (name "P_BAT2+") (class "Default")
      (node (ref "CON_PROG") (pin "15") (pinfunction "15_15") (pintype "bidirectional"))
      (node (ref "SWITCH_PWR") (pin "6") (pinfunction "S1_6") (pintype "passive"))
    )
    (net (code "54") (name "RESET") (class "Default")
      (node (ref "CON_PROG") (pin "7") (pinfunction "7_7") (pintype "bidirectional"))
      (node (ref "IC1") (pin "29") (pinfunction "PC6(/RESET/PCINT14)_29") (pintype "bidirectional"))
      (node (ref "R2") (pin "2") (pinfunction "2_2") (pintype "passive"))
    )
    (net (code "55") (name "RI2C_EN") (class "Default")
      (node (ref "IC1") (pin "19") (pinfunction "ADC6_19") (pintype "passive"))
    )
    (net (code "56") (name "RSCL") (class "Default")
      (node (ref "CON_PROG") (pin "8") (pinfunction "8_8") (pintype "bidirectional"))
      (node (ref "IC1") (pin "28") (pinfunction "PC5(ADC5/SCL/PCINT13)_28") (pintype "bidirectional"))
      (node (ref "IC2") (pin "1") (pinfunction "SCL_1") (pintype "bidirectional"))
      (node (ref "R34") (pin "1") (pinfunction "1_1") (pintype "passive"))
    )
    (net (code "57") (name "RSDA") (class "Default")
      (node (ref "CON_PROG") (pin "9") (pinfunction "9_9") (pintype "bidirectional"))
      (node (ref "IC1") (pin "27") (pinfunction "PC4(ADC4/SDA/PCINT12)_27") (pintype "bidirectional"))
      (node (ref "IC2") (pin "2") (pinfunction "SDA_2") (pintype "bidirectional"))
      (node (ref "R35") (pin "1") (pinfunction "1_1") (pintype "passive"))
    )
    (net (code "58") (name "RXD") (class "Default")
      (node (ref "IC1") (pin "30") (pinfunction "PD0(RXD/PCINT16)_30") (pintype "bidirectional"))
      (node (ref "IC3") (pin "3") (pinfunction "RXD_3") (pintype "bidirectional"))
    )
    (net (code "59") (name "RXIR") (class "Default")
      (node (ref "IC3") (pin "6") (pinfunction "IR_RXD_6") (pintype "bidirectional"))
      (node (ref "IC4") (pin "3") (pinfunction "RXD_3") (pintype "output"))
    )
    (net (code "60") (name "SCK") (class "Default")
      (node (ref "CON_PROG") (pin "18") (pinfunction "18_18") (pintype "bidirectional"))
      (node (ref "IC1") (pin "17") (pinfunction "PB5(SCK/PCINT5)_17") (pintype "bidirectional"))
    )
    (net (code "61") (name "SCL") (class "Default")
      (node (ref "IC2") (pin "5") (pinfunction "SC0_5") (pintype "bidirectional"))
      (node (ref "IC5") (pin "10") (pinfunction "SCL_10") (pintype "input"))
      (node (ref "IC6") (pin "7") (pinfunction "SCL_7") (pintype "input"))
      (node (ref "IC7") (pin "10") (pinfunction "SCL_10") (pintype "input"))
      (node (ref "IC8") (pin "7") (pinfunction "SCL_7") (pintype "input"))
      (node (ref "R8") (pin "1") (pinfunction "1_1") (pintype "passive"))
    )
    (net (code "62") (name "SDA") (class "Default")
      (node (ref "IC2") (pin "4") (pinfunction "SD0_4") (pintype "bidirectional"))
      (node (ref "IC5") (pin "9") (pinfunction "SDA_9") (pintype "bidirectional"))
      (node (ref "IC6") (pin "6") (pinfunction "SDA_6") (pintype "bidirectional"))
      (node (ref "IC7") (pin "9") (pinfunction "SDA_9") (pintype "bidirectional"))
      (node (ref "IC8") (pin "6") (pinfunction "SDA_6") (pintype "bidirectional"))
      (node (ref "R7") (pin "1") (pinfunction "1_1") (pintype "passive"))
    )
    (net (code "63") (name "SENS_MOTL1") (class "Default")
      (node (ref "IC5") (pin "3") (pinfunction "OUT1_3") (pintype "output"))
      (node (ref "IC6") (pin "1") (pinfunction "V1_1") (pintype "input"))
      (node (ref "R30") (pin "1") (pinfunction "1_1") (pintype "passive"))
    )
    (net (code "64") (name "SENS_MOTL2") (class "Default")
      (node (ref "IC6") (pin "2") (pinfunction "V2_2") (pintype "input"))
      (node (ref "MOT2") (pin "1") (pinfunction "P_1") (pintype "passive"))
      (node (ref "R30") (pin "2") (pinfunction "2_2") (pintype "passive"))
    )
    (net (code "65") (name "SENS_MOTR1") (class "Default")
      (node (ref "IC6") (pin "3") (pinfunction "V3_3") (pintype "input"))
      (node (ref "IC7") (pin "3") (pinfunction "OUT1_3") (pintype "output"))
      (node (ref "R32") (pin "1") (pinfunction "1_1") (pintype "passive"))
    )
    (net (code "66") (name "SENS_MOTR2") (class "Default")
      (node (ref "IC6") (pin "4") (pinfunction "V4_4") (pintype "input"))
      (node (ref "MOT4") (pin "1") (pinfunction "P_1") (pintype "passive"))
      (node (ref "R32") (pin "2") (pinfunction "2_2") (pintype "passive"))
    )
    (net (code "67") (name "SRXD") (class "Default")
      (node (ref "CON_PROG") (pin "11") (pinfunction "11_11") (pintype "bidirectional"))
      (node (ref "IC1") (pin "23") (pinfunction "PC0(ADC0/PCINT8)_23") (pintype "bidirectional"))
    )
    (net (code "68") (name "STXD") (class "Default")
      (node (ref "CON_PROG") (pin "10") (pinfunction "10_10") (pintype "bidirectional"))
      (node (ref "IC1") (pin "24") (pinfunction "PC1(ADC1/PCINT9)_24") (pintype "bidirectional"))
    )
    (net (code "69") (name "TXD") (class "Default")
      (node (ref "IC1") (pin "31") (pinfunction "PD1(TXD/PCINT17)_31") (pintype "bidirectional"))
      (node (ref "IC3") (pin "2") (pinfunction "TXD_2") (pintype "bidirectional"))
    )
    (net (code "70") (name "TXIR") (class "Default")
      (node (ref "IC3") (pin "7") (pinfunction "IR_TXD_7") (pintype "bidirectional"))
      (node (ref "IC4") (pin "2") (pinfunction "TXD_2") (pintype "input"))
    )
    (net (code "71") (name "VCC") (class "Default")
      (node (ref "C1") (pin "1") (pinfunction "1_1") (pintype "passive"))
      (node (ref "C5") (pin "1") (pinfunction "1_1") (pintype "passive"))
      (node (ref "CON_PROG") (pin "1") (pinfunction "1_1") (pintype "bidirectional"))
      (node (ref "D1") (pin "C") (pinfunction "C_C") (pintype "passive"))
      (node (ref "D2") (pin "C") (pinfunction "C_C") (pintype "passive"))
      (node (ref "IC1") (pin "18") (pinfunction "AVCC_18") (pintype "passive"))
      (node (ref "IC1") (pin "4") (pinfunction "VCC_4") (pintype "power_in"))
      (node (ref "IC1") (pin "6") (pinfunction "VCC_6") (pintype "power_in"))
      (node (ref "IC2") (pin "3") (pinfunction "VCC_3") (pintype "bidirectional"))
      (node (ref "IC3") (pin "8") (pinfunction "VCC_8") (pintype "bidirectional"))
      (node (ref "IC4") (pin "5") (pinfunction "VCC_5") (pintype "power_in"))
      (node (ref "IC5") (pin "4") (pinfunction "VCC_4") (pintype "power_in"))
      (node (ref "IC6") (pin "10") (pinfunction "VCC_10") (pintype "power_in"))
      (node (ref "IC7") (pin "4") (pinfunction "VCC_4") (pintype "power_in"))
      (node (ref "IC7") (pin "7") (pinfunction "A0_7") (pintype "input"))
      (node (ref "IC8") (pin "10") (pinfunction "VCC_10") (pintype "power_in"))
      (node (ref "IC8") (pin "8") (pinfunction "ADR0_8") (pintype "input"))
      (node (ref "Q1") (pin "4") (pinfunction "VCC_4") (pintype "power_in"))
      (node (ref "Q5") (pin "C") (pinfunction "C_C") (pintype "passive"))
      (node (ref "Q6") (pin "C") (pinfunction "C_C") (pintype "passive"))
      (node (ref "Q7") (pin "C") (pinfunction "C_C") (pintype "passive"))
      (node (ref "Q8") (pin "C") (pinfunction "C_C") (pintype "passive"))
      (node (ref "R1") (pin "1") (pinfunction "1_1") (pintype "passive"))
      (node (ref "R10") (pin "1") (pinfunction "1_1") (pintype "passive"))
      (node (ref "R2") (pin "1") (pinfunction "1_1") (pintype "passive"))
      (node (ref "R33") (pin "2") (pinfunction "2_2") (pintype "passive"))
      (node (ref "R34") (pin "2") (pinfunction "2_2") (pintype "passive"))
      (node (ref "R35") (pin "2") (pinfunction "2_2") (pintype "passive"))
      (node (ref "R4") (pin "1") (pinfunction "1_1") (pintype "passive"))
      (node (ref "R5") (pin "1") (pinfunction "1_1") (pintype "passive"))
      (node (ref "R7") (pin "2") (pinfunction "2_2") (pintype "passive"))
      (node (ref "R8") (pin "2") (pinfunction "2_2") (pintype "passive"))
    )
    (net (code "72") (name "unconnected-(CON_PROG-Pad6)") (class "Default")
      (node (ref "CON_PROG") (pin "6") (pinfunction "6_6") (pintype "bidirectional"))
    )
    (net (code "73") (name "unconnected-(IC2-SC1-Pad8)") (class "Default")
      (node (ref "IC2") (pin "8") (pinfunction "SC1_8") (pintype "bidirectional"))
    )
    (net (code "74") (name "unconnected-(IC2-SD1-Pad7)") (class "Default")
      (node (ref "IC2") (pin "7") (pinfunction "SD1_7") (pintype "bidirectional"))
    )
    (net (code "75") (name "unconnected-(IC5-FAULTN-Pad6)") (class "Default")
      (node (ref "IC5") (pin "6") (pinfunction "FAULTN_6") (pintype "output"))
    )
    (net (code "76") (name "unconnected-(IC7-FAULTN-Pad6)") (class "Default")
      (node (ref "IC7") (pin "6") (pinfunction "FAULTN_6") (pintype "output"))
    )
  )
)
